# 7-seg_display.net
KiCad netlist of a schematic drawn in EasyEDA
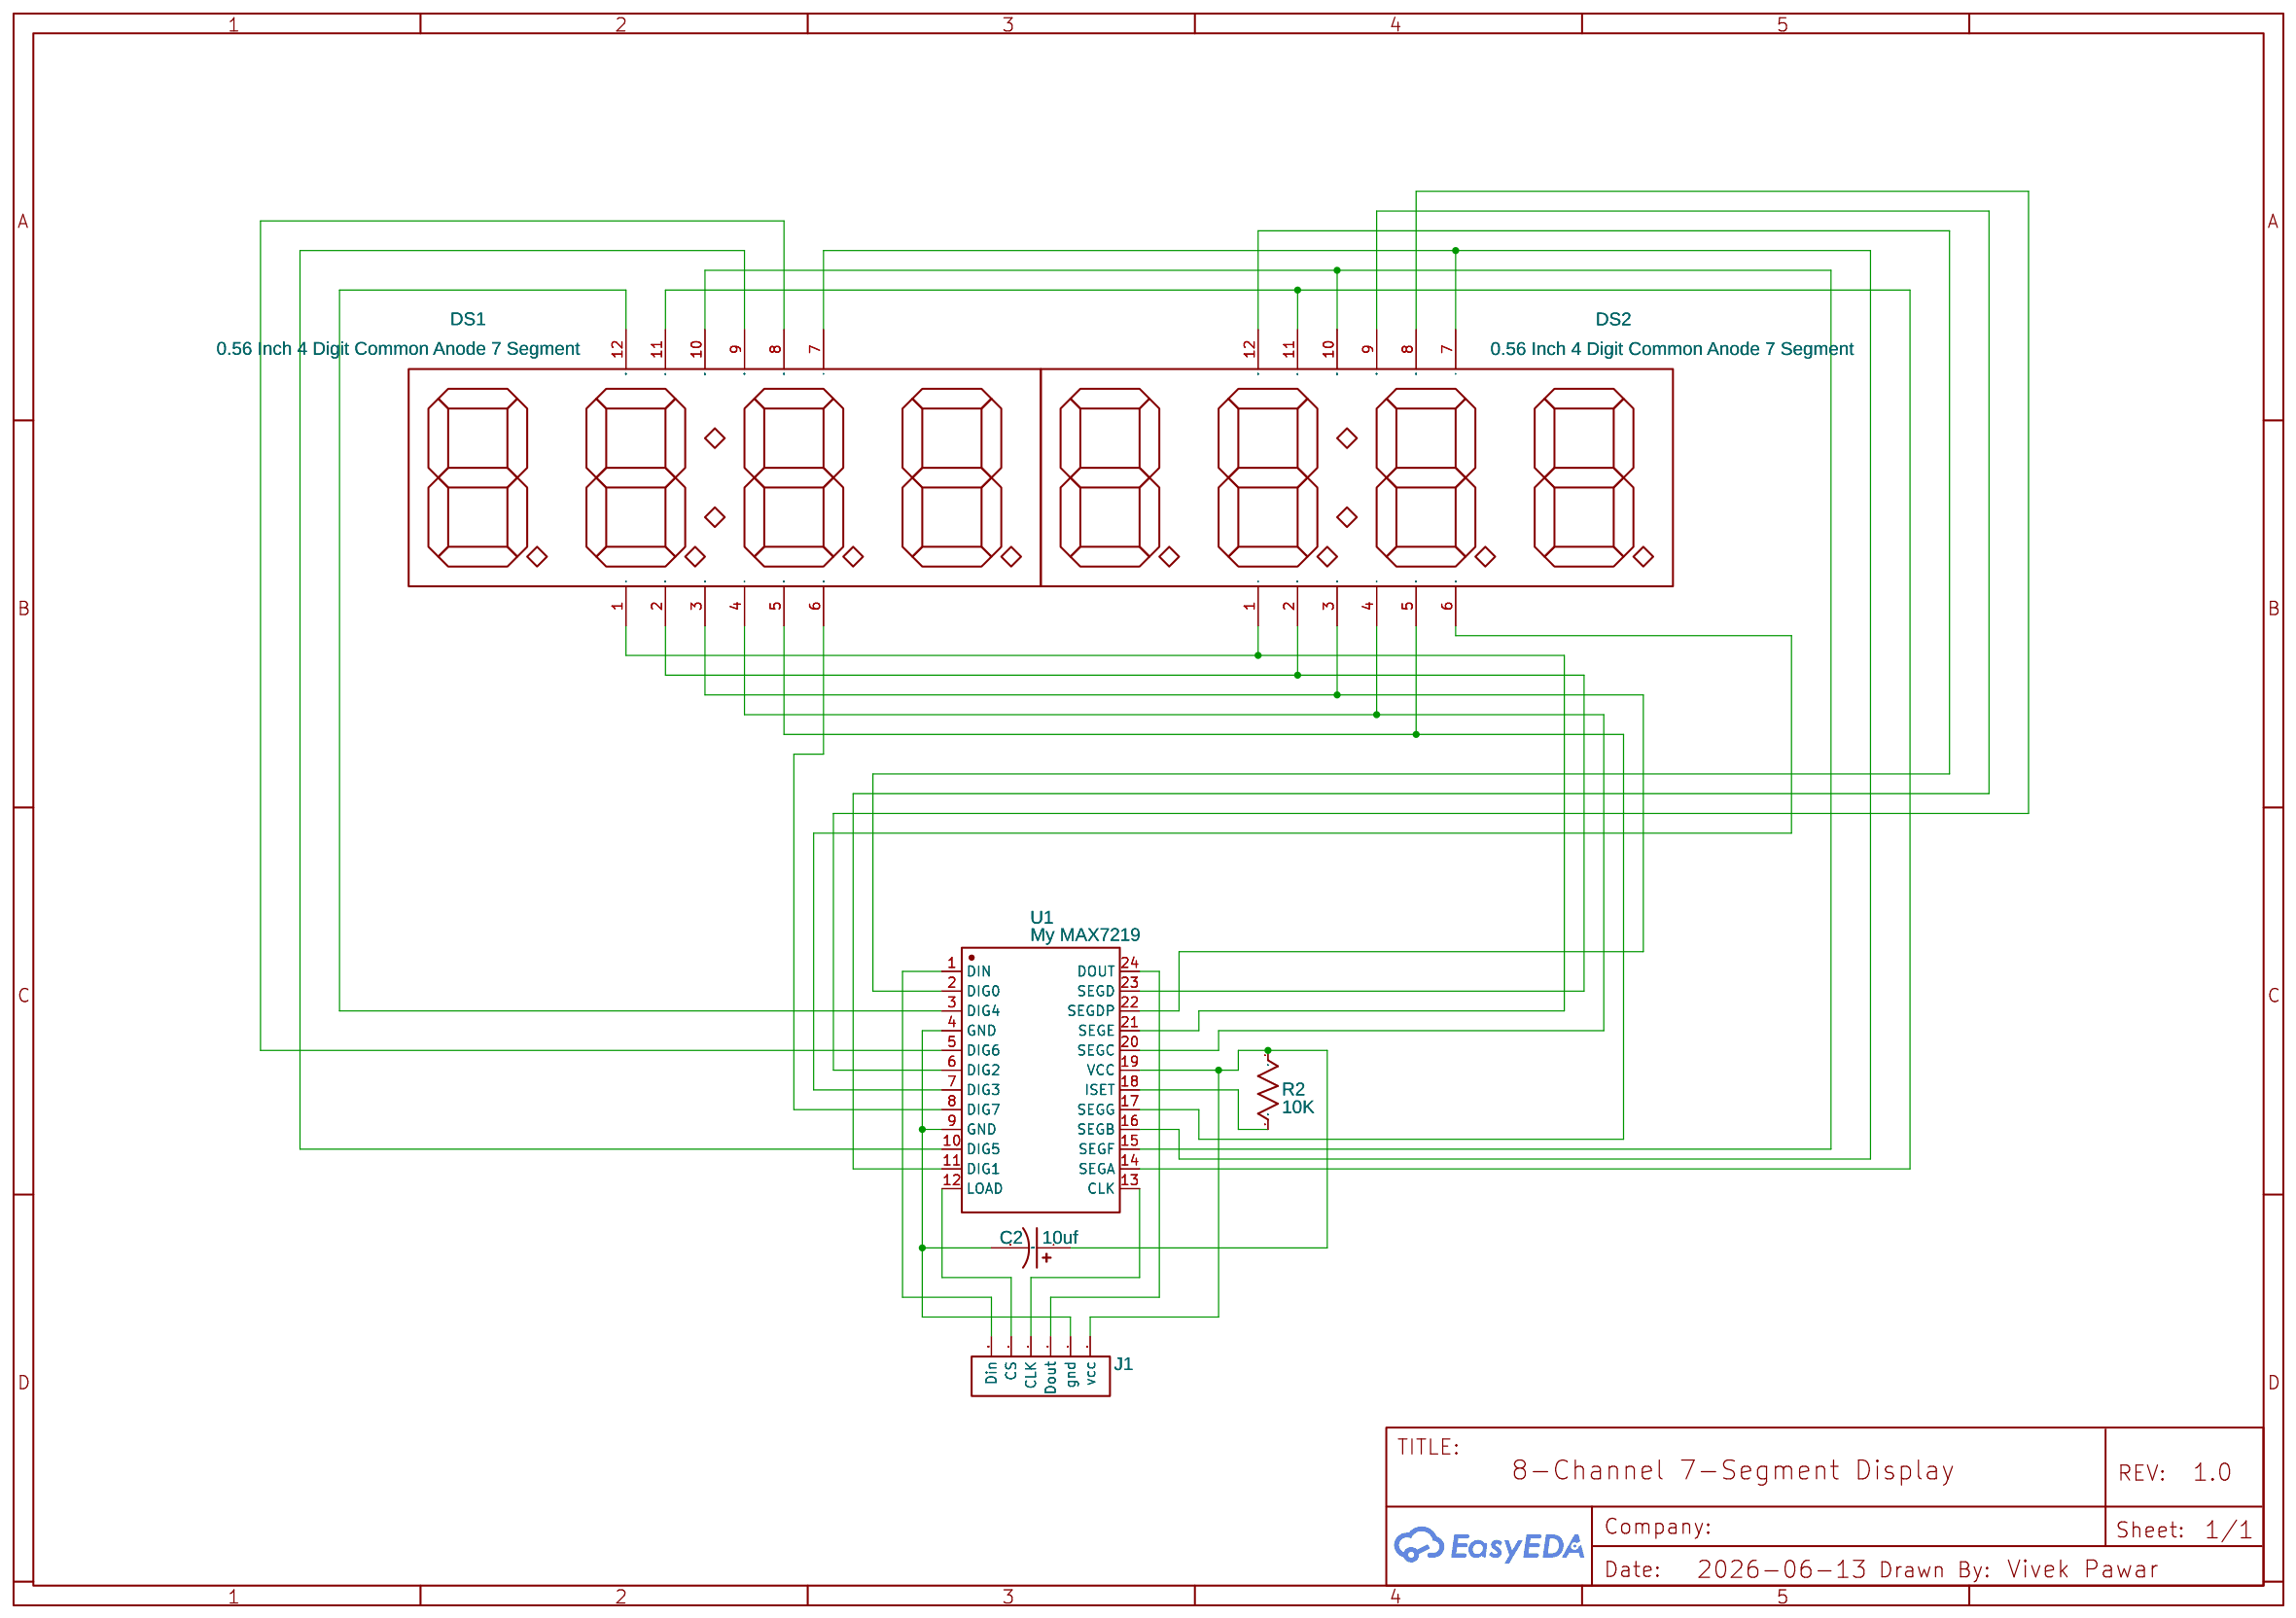
[diagram p0: schematic sheet]

(export (version "E")
  (design (tool "Eeschema 10.0.6"))
  (components
    (comp (ref "C2") (value "10uf") (libsource (lib "") (part "CE_TH_D3.0×F1.5_US")))
    (comp (ref "DS1")
      (value "0.56 Inch 4 Digit Common Anode 7 Segment")
      (fields (field (name "Manufacturer Part") "0.56 Inch 4 Digit Common Anode 7 Segment Display Clock"))
      (libsource (lib "") (part "0.56 Inch 4 Digit Common Anode 7 Segment"))
    )
    (comp (ref "DS2")
      (value "0.56 Inch 4 Digit Common Anode 7 Segment")
      (fields (field (name "Manufacturer Part") "0.56 Inch 4 Digit Common Anode 7 Segment Display Clock"))
      (libsource (lib "") (part "0.56 Inch 4 Digit Common Anode 7 Segment"))
    )
    (comp (ref "J1") (value "HDR-M-2.54_1x6") (libsource (lib "") (part "HDR-M-2.54_1x6")))
    (comp (ref "R2") (value "10K") (libsource (lib "") (part "R_0603_US")))
    (comp (ref "U1") (value "My MAX7219") (libsource (lib "") (part "My MAX7219")))
  )
  (nets
    (net (code "1") (name "Net-(J1-CLK)") (class "Default")
      (node (ref "J1") (pin "4") (pinfunction "CLK_4") (pintype "input"))
      (node (ref "U1") (pin "13") (pinfunction "CLK_13") (pintype "unspecified"))
    )
    (net (code "2") (name "Net-(J1-CS)") (class "Default")
      (node (ref "J1") (pin "5") (pinfunction "CS_5") (pintype "input"))
      (node (ref "U1") (pin "12") (pinfunction "LOAD_12") (pintype "unspecified"))
    )
    (net (code "3") (name "Net-(J1-Din)") (class "Default")
      (node (ref "J1") (pin "6") (pinfunction "Din_6") (pintype "input"))
      (node (ref "U1") (pin "1") (pinfunction "DIN_1") (pintype "unspecified"))
    )
    (net (code "4") (name "Net-(J1-Dout)") (class "Default")
      (node (ref "J1") (pin "3") (pinfunction "Dout_3") (pintype "input"))
      (node (ref "U1") (pin "24") (pinfunction "DOUT_24") (pintype "unspecified"))
    )
    (net (code "5") (name "Net-(J1-gnd)") (class "Default")
      (node (ref "C2") (pin "2") (pinfunction "2_2") (pintype "unspecified"))
      (node (ref "J1") (pin "2") (pinfunction "gnd_2") (pintype "input"))
      (node (ref "U1") (pin "4") (pinfunction "GND_4") (pintype "unspecified"))
      (node (ref "U1") (pin "9") (pinfunction "GND_9") (pintype "unspecified"))
    )
    (net (code "6") (name "Net-(J1-vcc)") (class "Default")
      (node (ref "C2") (pin "1") (pinfunction "1_1") (pintype "unspecified"))
      (node (ref "J1") (pin "1") (pinfunction "vcc_1") (pintype "input"))
      (node (ref "R2") (pin "1") (pinfunction "1_1") (pintype "unspecified"))
      (node (ref "U1") (pin "19") (pinfunction "VCC_19") (pintype "unspecified"))
    )
    (net (code "7") (name "Net-(U1-DIG0)") (class "Default")
      (node (ref "DS2") (pin "12") (pinfunction "12_12") (pintype "input"))
      (node (ref "U1") (pin "2") (pinfunction "DIG0_2") (pintype "unspecified"))
    )
    (net (code "8") (name "Net-(U1-DIG1)") (class "Default")
      (node (ref "DS2") (pin "9") (pinfunction "9_9") (pintype "input"))
      (node (ref "U1") (pin "11") (pinfunction "DIG1_11") (pintype "unspecified"))
    )
    (net (code "9") (name "Net-(U1-DIG2)") (class "Default")
      (node (ref "DS2") (pin "8") (pinfunction "8_8") (pintype "input"))
      (node (ref "U1") (pin "6") (pinfunction "DIG2_6") (pintype "unspecified"))
    )
    (net (code "10") (name "Net-(U1-DIG3)") (class "Default")
      (node (ref "DS2") (pin "6") (pinfunction "6_6") (pintype "input"))
      (node (ref "U1") (pin "7") (pinfunction "DIG3_7") (pintype "unspecified"))
    )
    (net (code "11") (name "Net-(U1-DIG4)") (class "Default")
      (node (ref "DS1") (pin "12") (pinfunction "12_12") (pintype "input"))
      (node (ref "U1") (pin "3") (pinfunction "DIG4_3") (pintype "unspecified"))
    )
    (net (code "12") (name "Net-(U1-DIG5)") (class "Default")
      (node (ref "DS1") (pin "9") (pinfunction "9_9") (pintype "input"))
      (node (ref "U1") (pin "10") (pinfunction "DIG5_10") (pintype "unspecified"))
    )
    (net (code "13") (name "Net-(U1-DIG6)") (class "Default")
      (node (ref "DS1") (pin "8") (pinfunction "8_8") (pintype "input"))
      (node (ref "U1") (pin "5") (pinfunction "DIG6_5") (pintype "unspecified"))
    )
    (net (code "14") (name "Net-(U1-DIG7)") (class "Default")
      (node (ref "DS1") (pin "6") (pinfunction "6_6") (pintype "input"))
      (node (ref "U1") (pin "8") (pinfunction "DIG7_8") (pintype "unspecified"))
    )
    (net (code "15") (name "Net-(U1-ISET)") (class "Default")
      (node (ref "R2") (pin "2") (pinfunction "2_2") (pintype "unspecified"))
      (node (ref "U1") (pin "18") (pinfunction "ISET_18") (pintype "unspecified"))
    )
    (net (code "16") (name "Net-(U1-SEGA)") (class "Default")
      (node (ref "DS1") (pin "11") (pinfunction "11_11") (pintype "input"))
      (node (ref "DS2") (pin "11") (pinfunction "11_11") (pintype "input"))
      (node (ref "U1") (pin "14") (pinfunction "SEGA_14") (pintype "unspecified"))
    )
    (net (code "17") (name "Net-(U1-SEGB)") (class "Default")
      (node (ref "DS1") (pin "7") (pinfunction "7_7") (pintype "input"))
      (node (ref "DS2") (pin "7") (pinfunction "7_7") (pintype "input"))
      (node (ref "U1") (pin "16") (pinfunction "SEGB_16") (pintype "unspecified"))
    )
    (net (code "18") (name "Net-(U1-SEGC)") (class "Default")
      (node (ref "DS1") (pin "4") (pinfunction "4_4") (pintype "input"))
      (node (ref "DS2") (pin "4") (pinfunction "4_4") (pintype "input"))
      (node (ref "U1") (pin "20") (pinfunction "SEGC_20") (pintype "unspecified"))
    )
    (net (code "19") (name "Net-(U1-SEGD)") (class "Default")
      (node (ref "DS1") (pin "2") (pinfunction "2_2") (pintype "input"))
      (node (ref "DS2") (pin "2") (pinfunction "2_2") (pintype "input"))
      (node (ref "U1") (pin "23") (pinfunction "SEGD_23") (pintype "unspecified"))
    )
    (net (code "20") (name "Net-(U1-SEGDP)") (class "Default")
      (node (ref "DS1") (pin "3") (pinfunction "3_3") (pintype "input"))
      (node (ref "DS2") (pin "3") (pinfunction "3_3") (pintype "input"))
      (node (ref "U1") (pin "22") (pinfunction "SEGDP_22") (pintype "unspecified"))
    )
    (net (code "21") (name "Net-(U1-SEGE)") (class "Default")
      (node (ref "DS1") (pin "1") (pinfunction "1_1") (pintype "input"))
      (node (ref "DS2") (pin "1") (pinfunction "1_1") (pintype "input"))
      (node (ref "U1") (pin "21") (pinfunction "SEGE_21") (pintype "unspecified"))
    )
    (net (code "22") (name "Net-(U1-SEGF)") (class "Default")
      (node (ref "DS1") (pin "10") (pinfunction "10_10") (pintype "input"))
      (node (ref "DS2") (pin "10") (pinfunction "10_10") (pintype "input"))
      (node (ref "U1") (pin "15") (pinfunction "SEGF_15") (pintype "unspecified"))
    )
    (net (code "23") (name "Net-(U1-SEGG)") (class "Default")
      (node (ref "DS1") (pin "5") (pinfunction "5_5") (pintype "input"))
      (node (ref "DS2") (pin "5") (pinfunction "5_5") (pintype "input"))
      (node (ref "U1") (pin "17") (pinfunction "SEGG_17") (pintype "unspecified"))
    )
  )
)
